# sokolov_control_board_1.net
KiCad netlist of a schematic drawn in Altium Designer
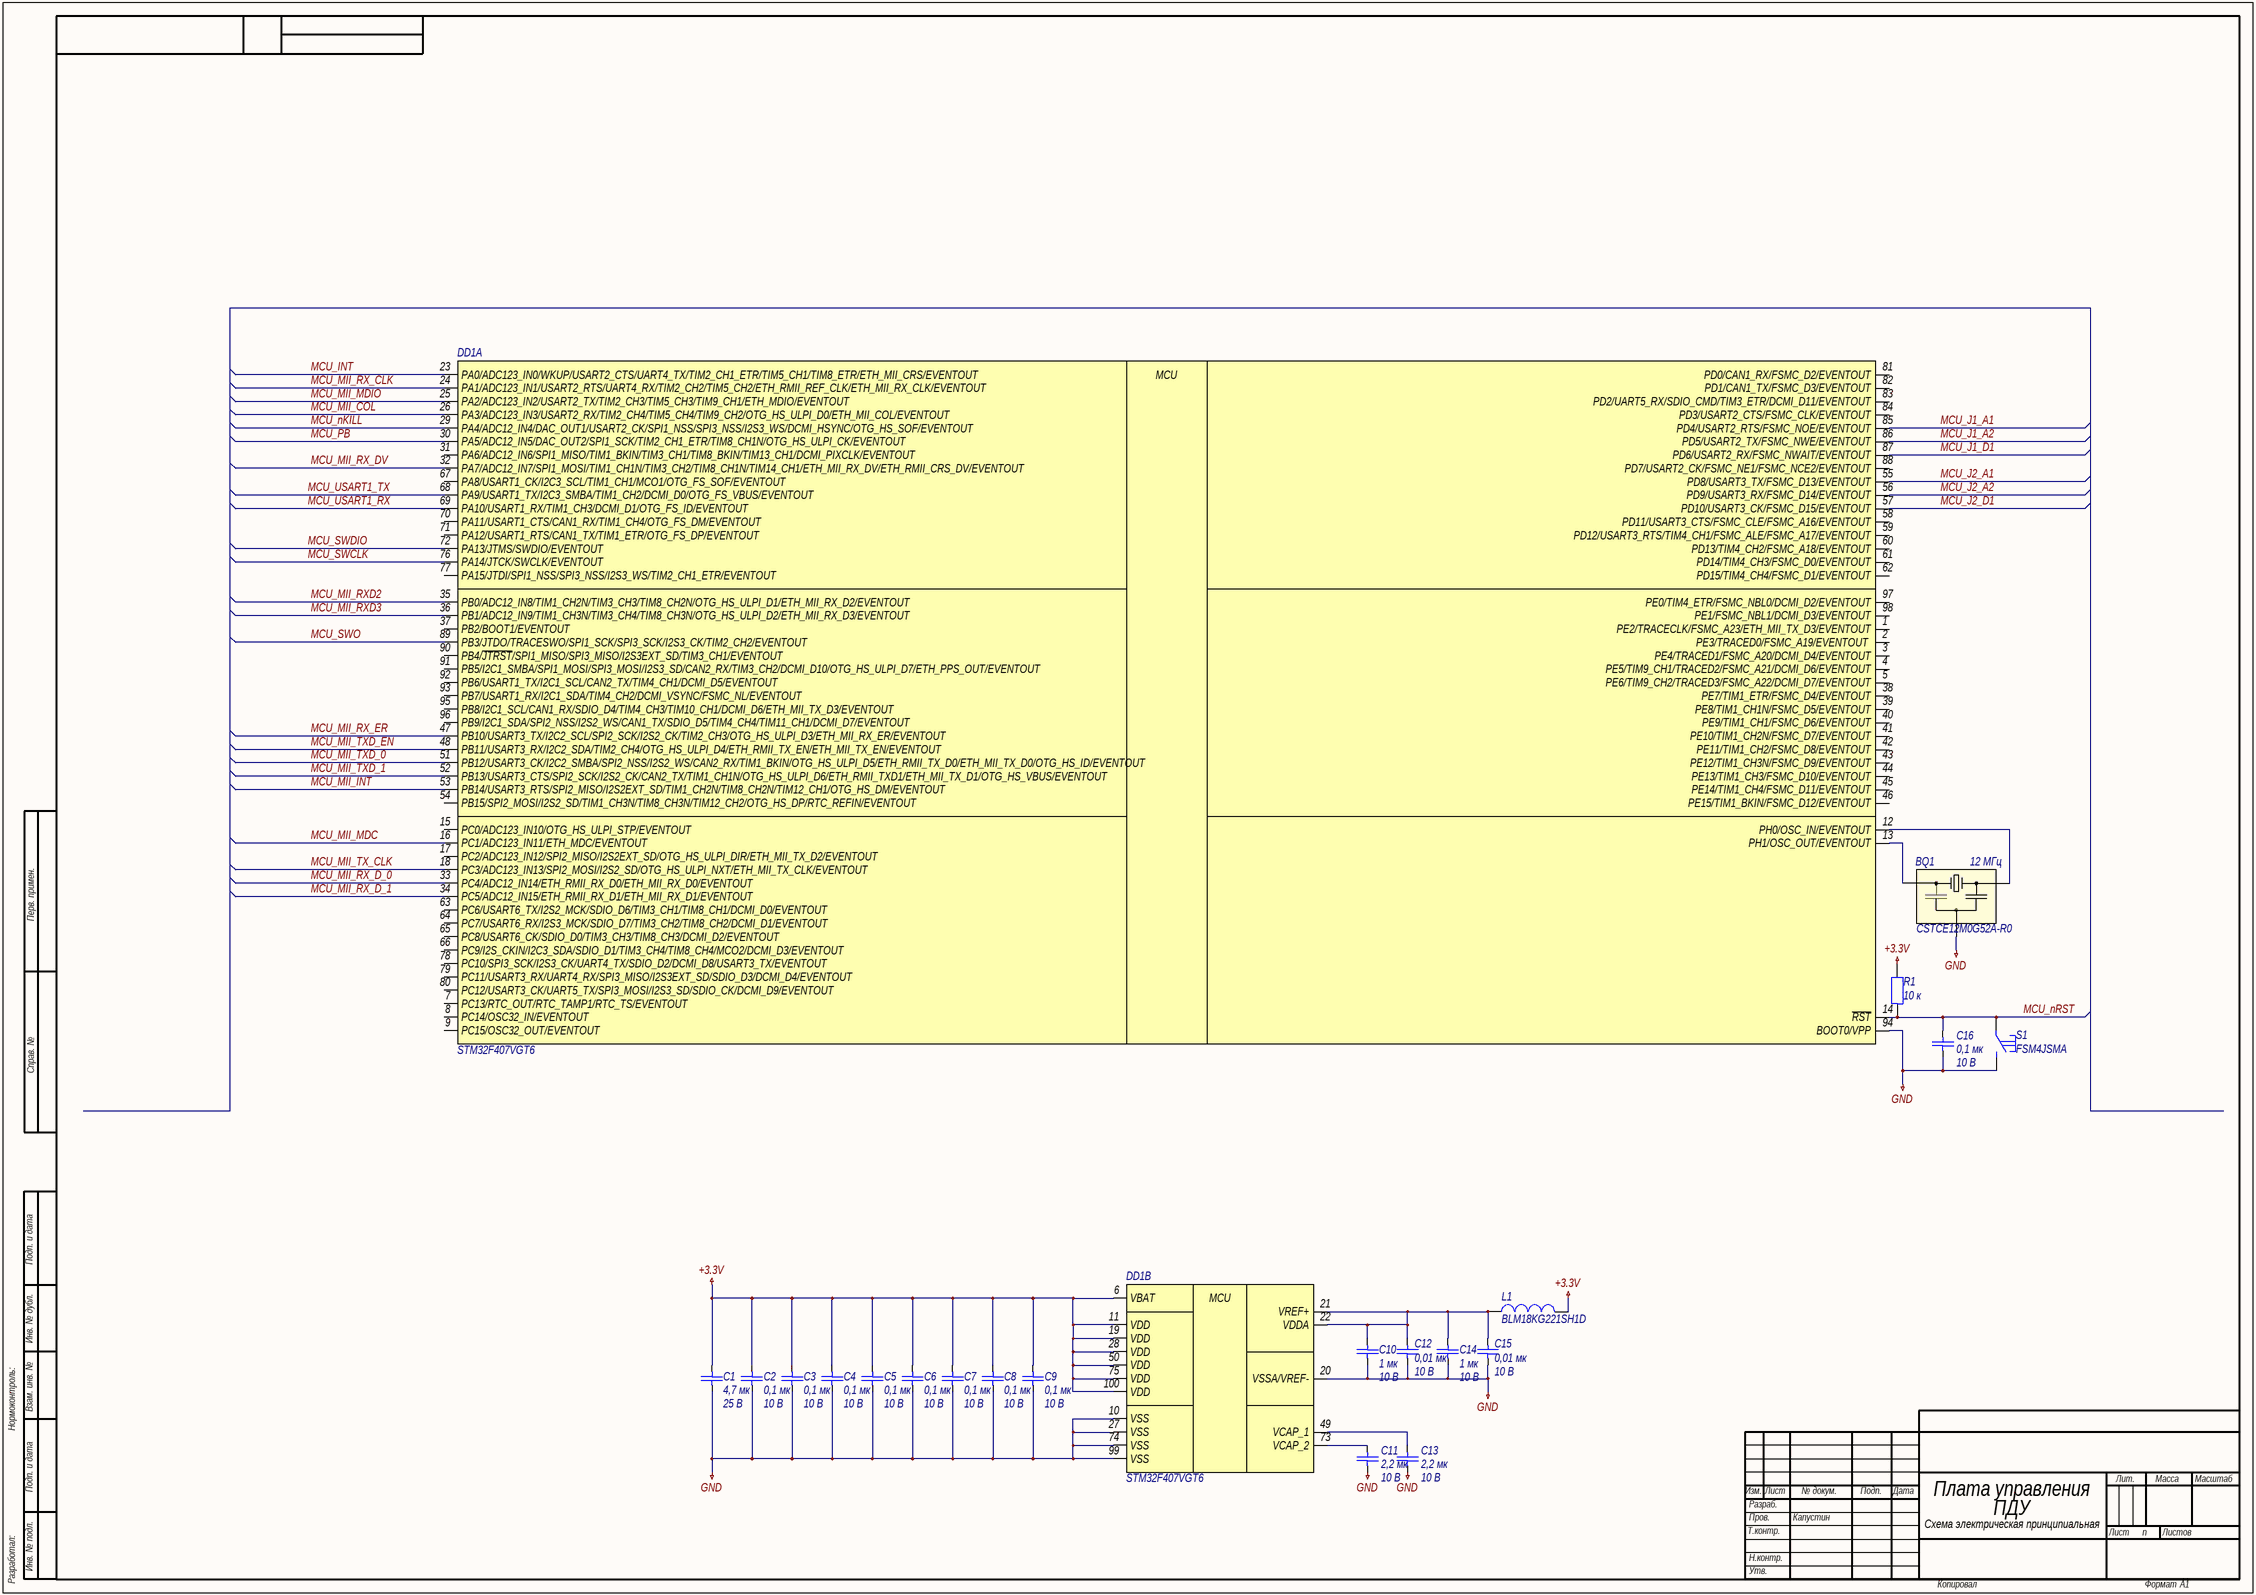
[diagram p0: sokolov_control_board_1.SchDoc]

(export (version "E")
  (design (tool "Eeschema 10.0.6"))
  (components
    (comp (ref "BQ1")
      (value "CSTCE12M0G52A-R0")
      (footprint "CSTCE-3-P120-320X130X70")
      (description "=Описание")
      (fields (field (name "ЧАСТОТA") "12 МГц"))
      (libsource (lib "Database_Students") (part "CSTCE12M0G52A-R0"))
    )
    (comp (ref "C1")
      (value "4,7 мк")
      (footprint "C0805")
      (description "=Описание")
      (fields (field (name "НАПРЯЖЕНИЕ") "25 В"))
      (libsource (lib "Database_Students") (part "CAPACITOR-NONPOLAR"))
    )
    (comp (ref "C2")
      (value "0,1 мк")
      (footprint "C0603")
      (description "=Описание")
      (fields (field (name "НАПРЯЖЕНИЕ") "10 В"))
      (libsource (lib "Database_Students") (part "CAPACITOR-NONPOLAR"))
    )
    (comp (ref "C3")
      (value "0,1 мк")
      (footprint "C0603")
      (description "=Описание")
      (fields (field (name "НАПРЯЖЕНИЕ") "10 В"))
      (libsource (lib "Database_Students") (part "CAPACITOR-NONPOLAR"))
    )
    (comp (ref "C4")
      (value "0,1 мк")
      (footprint "C0603")
      (description "=Описание")
      (fields (field (name "НАПРЯЖЕНИЕ") "10 В"))
      (libsource (lib "Database_Students") (part "CAPACITOR-NONPOLAR"))
    )
    (comp (ref "C5")
      (value "0,1 мк")
      (footprint "C0603")
      (description "=Описание")
      (fields (field (name "НАПРЯЖЕНИЕ") "10 В"))
      (libsource (lib "Database_Students") (part "CAPACITOR-NONPOLAR"))
    )
    (comp (ref "C6")
      (value "0,1 мк")
      (footprint "C0603")
      (description "=Описание")
      (fields (field (name "НАПРЯЖЕНИЕ") "10 В"))
      (libsource (lib "Database_Students") (part "CAPACITOR-NONPOLAR"))
    )
    (comp (ref "C7")
      (value "0,1 мк")
      (footprint "C0603")
      (description "=Описание")
      (fields (field (name "НАПРЯЖЕНИЕ") "10 В"))
      (libsource (lib "Database_Students") (part "CAPACITOR-NONPOLAR"))
    )
    (comp (ref "C8")
      (value "0,1 мк")
      (footprint "C0603")
      (description "=Описание")
      (fields (field (name "НАПРЯЖЕНИЕ") "10 В"))
      (libsource (lib "Database_Students") (part "CAPACITOR-NONPOLAR"))
    )
    (comp (ref "C9")
      (value "0,1 мк")
      (footprint "C0603")
      (description "=Описание")
      (fields (field (name "НАПРЯЖЕНИЕ") "10 В"))
      (libsource (lib "Database_Students") (part "CAPACITOR-NONPOLAR"))
    )
    (comp (ref "C10")
      (value "1 мк")
      (footprint "C0603")
      (description "=Описание")
      (fields (field (name "НАПРЯЖЕНИЕ") "10 В"))
      (libsource (lib "Database_Students") (part "CAPACITOR-NONPOLAR"))
    )
    (comp (ref "C11")
      (value "2,2 мк")
      (footprint "C0603")
      (description "=Описание")
      (fields (field (name "НАПРЯЖЕНИЕ") "10 В"))
      (libsource (lib "Database_Students") (part "CAPACITOR-NONPOLAR"))
    )
    (comp (ref "C12")
      (value "0,01 мк")
      (footprint "C0603")
      (description "=Описание")
      (fields (field (name "НАПРЯЖЕНИЕ") "10 В"))
      (libsource (lib "Database_Students") (part "CAPACITOR-NONPOLAR"))
    )
    (comp (ref "C13")
      (value "2,2 мк")
      (footprint "C0603")
      (description "=Описание")
      (fields (field (name "НАПРЯЖЕНИЕ") "10 В"))
      (libsource (lib "Database_Students") (part "CAPACITOR-NONPOLAR"))
    )
    (comp (ref "C14")
      (value "1 мк")
      (footprint "C0603")
      (description "=Описание")
      (fields (field (name "НАПРЯЖЕНИЕ") "10 В"))
      (libsource (lib "Database_Students") (part "CAPACITOR-NONPOLAR"))
    )
    (comp (ref "C15")
      (value "0,01 мк")
      (footprint "C0603")
      (description "=Описание")
      (fields (field (name "НАПРЯЖЕНИЕ") "10 В"))
      (libsource (lib "Database_Students") (part "CAPACITOR-NONPOLAR"))
    )
    (comp (ref "C16")
      (value "0,1 мк")
      (footprint "C0603")
      (description "=Описание")
      (fields (field (name "НАПРЯЖЕНИЕ") "10 В"))
      (libsource (lib "Database_Students") (part "CAPACITOR-NONPOLAR"))
    )
    (comp (ref "DD1")
      (value "STM32F407VGT6")
      (footprint "LQFP-100-P50-1400X1400X160-L60X22")
      (description "=Описание")
      (libsource (lib "Database_Students") (part "STM32F407VGT6"))
    )
    (comp (ref "L1")
      (value "BLM18KG221SH1D")
      (footprint "BLM-2-0603")
      (description "=Описание")
      (libsource (lib "Database_Students") (part "FERRITE-BEAD"))
    )
    (comp (ref "R1")
      (value "10 к")
      (footprint "R0603")
      (description "=Описание")
      (libsource (lib "Database_Students") (part "RESISTOR-COMMON"))
    )
    (comp (ref "S1")
      (value "FSM4JSMA")
      (footprint "FSM4JSMA")
      (description "=Описание")
      (libsource (lib "Database_Students") (part "BUTTON"))
    )
  )
  (nets
    (net (code "1") (name "+3.3V") (class "Default")
      (node (ref "C1") (pin "2") (pinfunction "2_2") (pintype "passive"))
      (node (ref "C2") (pin "2") (pinfunction "2_2") (pintype "passive"))
      (node (ref "C3") (pin "2") (pinfunction "2_2") (pintype "passive"))
      (node (ref "C4") (pin "2") (pinfunction "2_2") (pintype "passive"))
      (node (ref "C5") (pin "2") (pinfunction "2_2") (pintype "passive"))
      (node (ref "C6") (pin "2") (pinfunction "2_2") (pintype "passive"))
      (node (ref "C7") (pin "2") (pinfunction "2_2") (pintype "passive"))
      (node (ref "C8") (pin "2") (pinfunction "2_2") (pintype "passive"))
      (node (ref "C9") (pin "2") (pinfunction "2_2") (pintype "passive"))
      (node (ref "DD1") (pin "100") (pinfunction "VDD_100") (pintype "passive"))
      (node (ref "DD1") (pin "11") (pinfunction "VDD_11") (pintype "passive"))
      (node (ref "DD1") (pin "19") (pinfunction "VDD_19") (pintype "passive"))
      (node (ref "DD1") (pin "28") (pinfunction "VDD_28") (pintype "passive"))
      (node (ref "DD1") (pin "50") (pinfunction "VDD_50") (pintype "passive"))
      (node (ref "DD1") (pin "6") (pinfunction "VBAT_6") (pintype "passive"))
      (node (ref "DD1") (pin "75") (pinfunction "VDD_75") (pintype "passive"))
      (node (ref "L1") (pin "2") (pinfunction "2_2") (pintype "passive"))
      (node (ref "R1") (pin "2") (pinfunction "2_2") (pintype "passive"))
    )
    (net (code "2") (name "/MCU_INT") (class "Default")
      (node (ref "DD1") (pin "23") (pinfunction "PA0/ADC123_IN0/WKUP/USART2_CTS/UART4_TX/TIM2_CH1_ETR/TIM5_CH1/TIM8_ETR/ETH_MII_CRS/EVENTOUT_23") (pintype "passive"))
    )
    (net (code "3") (name "/MCU_J1_A1") (class "Default")
      (node (ref "DD1") (pin "85") (pinfunction "PD4/USART2_RTS/FSMC_NOE/EVENTOUT_85") (pintype "passive"))
    )
    (net (code "4") (name "/MCU_J1_A2") (class "Default")
      (node (ref "DD1") (pin "86") (pinfunction "PD5/USART2_TX/FSMC_NWE/EVENTOUT_86") (pintype "passive"))
    )
    (net (code "5") (name "/MCU_J1_D1") (class "Default")
      (node (ref "DD1") (pin "87") (pinfunction "PD6/USART2_RX/FSMC_NWAIT/EVENTOUT_87") (pintype "passive"))
    )
    (net (code "6") (name "/MCU_J2_A1") (class "Default")
      (node (ref "DD1") (pin "55") (pinfunction "PD8/USART3_TX/FSMC_D13/EVENTOUT_55") (pintype "passive"))
    )
    (net (code "7") (name "/MCU_J2_A2") (class "Default")
      (node (ref "DD1") (pin "56") (pinfunction "PD9/USART3_RX/FSMC_D14/EVENTOUT_56") (pintype "passive"))
    )
    (net (code "8") (name "/MCU_J2_D1") (class "Default")
      (node (ref "DD1") (pin "57") (pinfunction "PD10/USART3_CK/FSMC_D15/EVENTOUT_57") (pintype "passive"))
    )
    (net (code "9") (name "/MCU_MII_COL") (class "Default")
      (node (ref "DD1") (pin "26") (pinfunction "PA3/ADC123_IN3/USART2_RX/TIM2_CH4/TIM5_CH4/TIM9_CH2/OTG_HS_ULPI_D0/ETH_MII_COL/EVENTOUT_26") (pintype "passive"))
    )
    (net (code "10") (name "/MCU_MII_INT") (class "Default")
      (node (ref "DD1") (pin "53") (pinfunction "PB14/USART3_RTS/SPI2_MISO/I2S2EXT_SD/TIM1_CH2N/TIM8_CH2N/TIM12_CH1/OTG_HS_DM/EVENTOUT_53") (pintype "passive"))
    )
    (net (code "11") (name "/MCU_MII_MDC") (class "Default")
      (node (ref "DD1") (pin "16") (pinfunction "PC1/ADC123_IN11/ETH_MDC/EVENTOUT_16") (pintype "passive"))
    )
    (net (code "12") (name "/MCU_MII_MDIO") (class "Default")
      (node (ref "DD1") (pin "25") (pinfunction "PA2/ADC123_IN2/USART2_TX/TIM2_CH3/TIM5_CH3/TIM9_CH1/ETH_MDIO/EVENTOUT_25") (pintype "passive"))
    )
    (net (code "13") (name "/MCU_MII_RXD2") (class "Default")
      (node (ref "DD1") (pin "35") (pinfunction "PB0/ADC12_IN8/TIM1_CH2N/TIM3_CH3/TIM8_CH2N/OTG_HS_ULPI_D1/ETH_MII_RX_D2/EVENTOUT_35") (pintype "passive"))
    )
    (net (code "14") (name "/MCU_MII_RXD3") (class "Default")
      (node (ref "DD1") (pin "36") (pinfunction "PB1/ADC12_IN9/TIM1_CH3N/TIM3_CH4/TIM8_CH3N/OTG_HS_ULPI_D2/ETH_MII_RX_D3/EVENTOUT_36") (pintype "passive"))
    )
    (net (code "15") (name "/MCU_MII_RX_CLK") (class "Default")
      (node (ref "DD1") (pin "24") (pinfunction "PA1/ADC123_IN1/USART2_RTS/UART4_RX/TIM2_CH2/TIM5_CH2/ETH_RMII_REF_CLK/ETH_MII_RX_CLK/EVENTOUT_24") (pintype "passive"))
    )
    (net (code "16") (name "/MCU_MII_RX_DV") (class "Default")
      (node (ref "DD1") (pin "32") (pinfunction "PA7/ADC12_IN7/SPI1_MOSI/TIM1_CH1N/TIM3_CH2/TIM8_CH1N/TIM14_CH1/ETH_MII_RX_DV/ETH_RMII_CRS_DV/EVENTOUT_32") (pintype "passive"))
    )
    (net (code "17") (name "/MCU_MII_RX_D_0") (class "Default")
      (node (ref "DD1") (pin "33") (pinfunction "PC4/ADC12_IN14/ETH_RMII_RX_D0/ETH_MII_RX_D0/EVENTOUT_33") (pintype "passive"))
    )
    (net (code "18") (name "/MCU_MII_RX_D_1") (class "Default")
      (node (ref "DD1") (pin "34") (pinfunction "PC5/ADC12_IN15/ETH_RMII_RX_D1/ETH_MII_RX_D1/EVENTOUT_34") (pintype "passive"))
    )
    (net (code "19") (name "/MCU_MII_RX_ER") (class "Default")
      (node (ref "DD1") (pin "47") (pinfunction "PB10/USART3_TX/I2C2_SCL/SPI2_SCK/I2S2_CK/TIM2_CH3/OTG_HS_ULPI_D3/ETH_MII_RX_ER/EVENTOUT_47") (pintype "passive"))
    )
    (net (code "20") (name "/MCU_MII_TXD_0") (class "Default")
      (node (ref "DD1") (pin "51") (pinfunction "PB12/USART3_CK/I2C2_SMBA/SPI2_NSS/I2S2_WS/CAN2_RX/TIM1_BKIN/OTG_HS_ULPI_D5/ETH_RMII_TX_D0/ETH_MII_TX_D0/OTG_HS_ID/EVENTOUT_51") (pintype "passive"))
    )
    (net (code "21") (name "/MCU_MII_TXD_1") (class "Default")
      (node (ref "DD1") (pin "52") (pinfunction "PB13/USART3_CTS/SPI2_SCK/I2S2_CK/CAN2_TX/TIM1_CH1N/OTG_HS_ULPI_D6/ETH_RMII_TXD1/ETH_MII_TX_D1/OTG_HS_VBUS/EVENTOUT_52") (pintype "passive"))
    )
    (net (code "22") (name "/MCU_MII_TXD_EN") (class "Default")
      (node (ref "DD1") (pin "48") (pinfunction "PB11/USART3_RX/I2C2_SDA/TIM2_CH4/OTG_HS_ULPI_D4/ETH_RMII_TX_EN/ETH_MII_TX_EN/EVENTOUT_48") (pintype "passive"))
    )
    (net (code "23") (name "/MCU_MII_TX_CLK") (class "Default")
      (node (ref "DD1") (pin "18") (pinfunction "PC3/ADC123_IN13/SPI2_MOSI/I2S2_SD/OTG_HS_ULPI_NXT/ETH_MII_TX_CLK/EVENTOUT_18") (pintype "passive"))
    )
    (net (code "24") (name "/MCU_PB") (class "Default")
      (node (ref "DD1") (pin "30") (pinfunction "PA5/ADC12_IN5/DAC_OUT2/SPI1_SCK/TIM2_CH1_ETR/TIM8_CH1N/OTG_HS_ULPI_CK/EVENTOUT_30") (pintype "passive"))
    )
    (net (code "25") (name "/MCU_SWCLK") (class "Default")
      (node (ref "DD1") (pin "76") (pinfunction "PA14/JTCK/SWCLK/EVENTOUT_76") (pintype "passive"))
    )
    (net (code "26") (name "/MCU_SWDIO") (class "Default")
      (node (ref "DD1") (pin "72") (pinfunction "PA13/JTMS/SWDIO/EVENTOUT_72") (pintype "passive"))
    )
    (net (code "27") (name "/MCU_SWO") (class "Default")
      (node (ref "DD1") (pin "89") (pinfunction "PB3/JTDO/TRACESWO/SPI1_SCK/SPI3_SCK/I2S3_CK/TIM2_CH2/EVENTOUT_89") (pintype "passive"))
    )
    (net (code "28") (name "/MCU_USART1_RX") (class "Default")
      (node (ref "DD1") (pin "69") (pinfunction "PA10/USART1_RX/TIM1_CH3/DCMI_D1/OTG_FS_ID/EVENTOUT_69") (pintype "passive"))
    )
    (net (code "29") (name "/MCU_USART1_TX") (class "Default")
      (node (ref "DD1") (pin "68") (pinfunction "PA9/USART1_TX/I2C3_SMBA/TIM1_CH2/DCMI_D0/OTG_FS_VBUS/EVENTOUT_68") (pintype "passive"))
    )
    (net (code "30") (name "/MCU_nKILL") (class "Default")
      (node (ref "DD1") (pin "29") (pinfunction "PA4/ADC12_IN4/DAC_OUT1/USART2_CK/SPI1_NSS/SPI3_NSS/I2S3_WS/DCMI_HSYNC/OTG_HS_SOF/EVENTOUT_29") (pintype "passive"))
    )
    (net (code "31") (name "/MCU_nRST") (class "Default")
      (node (ref "C16") (pin "1") (pinfunction "1_1") (pintype "passive"))
      (node (ref "DD1") (pin "14") (pinfunction "~{RST}_14") (pintype "passive"))
      (node (ref "R1") (pin "1") (pinfunction "1_1") (pintype "passive"))
      (node (ref "S1") (pin "1") (pinfunction "1_1") (pintype "passive"))
    )
    (net (code "32") (name "GND") (class "Default")
      (node (ref "BQ1") (pin "2") (pinfunction "2_2") (pintype "passive"))
      (node (ref "C1") (pin "1") (pinfunction "1_1") (pintype "passive"))
      (node (ref "C10") (pin "1") (pinfunction "1_1") (pintype "passive"))
      (node (ref "C11") (pin "2") (pinfunction "2_2") (pintype "passive"))
      (node (ref "C12") (pin "2") (pinfunction "2_2") (pintype "passive"))
      (node (ref "C13") (pin "2") (pinfunction "2_2") (pintype "passive"))
      (node (ref "C14") (pin "1") (pinfunction "1_1") (pintype "passive"))
      (node (ref "C15") (pin "2") (pinfunction "2_2") (pintype "passive"))
      (node (ref "C16") (pin "2") (pinfunction "2_2") (pintype "passive"))
      (node (ref "C2") (pin "1") (pinfunction "1_1") (pintype "passive"))
      (node (ref "C3") (pin "1") (pinfunction "1_1") (pintype "passive"))
      (node (ref "C4") (pin "1") (pinfunction "1_1") (pintype "passive"))
      (node (ref "C5") (pin "1") (pinfunction "1_1") (pintype "passive"))
      (node (ref "C6") (pin "1") (pinfunction "1_1") (pintype "passive"))
      (node (ref "C7") (pin "1") (pinfunction "1_1") (pintype "passive"))
      (node (ref "C8") (pin "1") (pinfunction "1_1") (pintype "passive"))
      (node (ref "C9") (pin "1") (pinfunction "1_1") (pintype "passive"))
      (node (ref "DD1") (pin "10") (pinfunction "VSS_10") (pintype "passive"))
      (node (ref "DD1") (pin "20") (pinfunction "VSSA/VREF-_20") (pintype "passive"))
      (node (ref "DD1") (pin "27") (pinfunction "VSS_27") (pintype "passive"))
      (node (ref "DD1") (pin "74") (pinfunction "VSS_74") (pintype "passive"))
      (node (ref "DD1") (pin "94") (pinfunction "BOOT0/VPP_94") (pintype "passive"))
      (node (ref "DD1") (pin "99") (pinfunction "VSS_99") (pintype "passive"))
      (node (ref "S1") (pin "2") (pinfunction "2_2") (pintype "passive"))
    )
    (net (code "33") (name "Net-(DD1A-PH0{slash}OSC_IN{slash}EVENTOUT)") (class "Default")
      (node (ref "BQ1") (pin "1") (pinfunction "1_1") (pintype "passive"))
      (node (ref "DD1") (pin "12") (pinfunction "PH0/OSC_IN/EVENTOUT_12") (pintype "passive"))
    )
    (net (code "34") (name "Net-(DD1A-PH1{slash}OSC_OUT{slash}EVENTOUT)") (class "Default")
      (node (ref "BQ1") (pin "3") (pinfunction "3_3") (pintype "passive"))
      (node (ref "DD1") (pin "13") (pinfunction "PH1/OSC_OUT/EVENTOUT_13") (pintype "passive"))
    )
    (net (code "35") (name "Net-(DD1B-VCAP_1)") (class "Default")
      (node (ref "C13") (pin "1") (pinfunction "1_1") (pintype "passive"))
      (node (ref "DD1") (pin "49") (pinfunction "VCAP_1_49") (pintype "passive"))
    )
    (net (code "36") (name "Net-(DD1B-VCAP_2)") (class "Default")
      (node (ref "C11") (pin "1") (pinfunction "1_1") (pintype "passive"))
      (node (ref "DD1") (pin "73") (pinfunction "VCAP_2_73") (pintype "passive"))
    )
    (net (code "37") (name "Net-(DD1B-VDDA)") (class "Default")
      (node (ref "C10") (pin "2") (pinfunction "2_2") (pintype "passive"))
      (node (ref "C12") (pin "1") (pinfunction "1_1") (pintype "passive"))
      (node (ref "C14") (pin "2") (pinfunction "2_2") (pintype "passive"))
      (node (ref "C15") (pin "1") (pinfunction "1_1") (pintype "passive"))
      (node (ref "DD1") (pin "21") (pinfunction "VREF+_21") (pintype "passive"))
      (node (ref "DD1") (pin "22") (pinfunction "VDDA_22") (pintype "passive"))
      (node (ref "L1") (pin "1") (pinfunction "1_1") (pintype "passive"))
    )
    (net (code "38") (name "unconnected-(DD1A-PA6{slash}ADC12_IN6{slash}SPI1_MISO{slash}TIM1_BKIN{slash}TIM3_CH1{slash}TIM8_BKIN{slash}TIM13_CH1{slash}DCMI_PIXCLK{slash}EVENTOUT-Pad31)") (class "Default")
      (node (ref "DD1") (pin "31") (pinfunction "PA6/ADC12_IN6/SPI1_MISO/TIM1_BKIN/TIM3_CH1/TIM8_BKIN/TIM13_CH1/DCMI_PIXCLK/EVENTOUT_31") (pintype "passive"))
    )
    (net (code "39") (name "unconnected-(DD1A-PA8{slash}USART1_CK{slash}I2C3_SCL{slash}TIM1_CH1{slash}MCO1{slash}OTG_FS_SOF{slash}EVENTOUT-Pad67)") (class "Default")
      (node (ref "DD1") (pin "67") (pinfunction "PA8/USART1_CK/I2C3_SCL/TIM1_CH1/MCO1/OTG_FS_SOF/EVENTOUT_67") (pintype "passive"))
    )
    (net (code "40") (name "unconnected-(DD1A-PA11{slash}USART1_CTS{slash}CAN1_RX{slash}TIM1_CH4{slash}OTG_FS_DM{slash}EVENTOUT-Pad70)") (class "Default")
      (node (ref "DD1") (pin "70") (pinfunction "PA11/USART1_CTS/CAN1_RX/TIM1_CH4/OTG_FS_DM/EVENTOUT_70") (pintype "passive"))
    )
    (net (code "41") (name "unconnected-(DD1A-PA12{slash}USART1_RTS{slash}CAN1_TX{slash}TIM1_ETR{slash}OTG_FS_DP{slash}EVENTOUT-Pad71)") (class "Default")
      (node (ref "DD1") (pin "71") (pinfunction "PA12/USART1_RTS/CAN1_TX/TIM1_ETR/OTG_FS_DP/EVENTOUT_71") (pintype "passive"))
    )
    (net (code "42") (name "unconnected-(DD1A-PA15{slash}JTDI{slash}SPI1_NSS{slash}SPI3_NSS{slash}I2S3_WS{slash}TIM2_CH1_ETR{slash}EVENTOUT-Pad77)") (class "Default")
      (node (ref "DD1") (pin "77") (pinfunction "PA15/JTDI/SPI1_NSS/SPI3_NSS/I2S3_WS/TIM2_CH1_ETR/EVENTOUT_77") (pintype "passive"))
    )
    (net (code "43") (name "unconnected-(DD1A-PB2{slash}BOOT1{slash}EVENTOUT-Pad37)") (class "Default")
      (node (ref "DD1") (pin "37") (pinfunction "PB2/BOOT1/EVENTOUT_37") (pintype "passive"))
    )
    (net (code "44") (name "unconnected-(DD1A-PB4{slash}~{JTRST}{slash}SPI1_MISO{slash}SPI3_MISO{slash}I2S3EXT_SD{slash}TIM3_CH1{slash}EVENTOUT-Pad90)") (class "Default")
      (node (ref "DD1") (pin "90") (pinfunction "PB4/~{JTRST}/SPI1_MISO/SPI3_MISO/I2S3EXT_SD/TIM3_CH1/EVENTOUT_90") (pintype "passive"))
    )
    (net (code "45") (name "unconnected-(DD1A-PB5{slash}I2C1_SMBA{slash}SPI1_MOSI{slash}SPI3_MOSI{slash}I2S3_SD{slash}CAN2_RX{slash}TIM3_CH2{slash}DCMI_D10{slash}OTG_HS_ULPI_D7{slash}ETH_PPS_OUT{slash}EVENTOUT-Pad91)") (class "Default")
      (node (ref "DD1") (pin "91") (pinfunction "PB5/I2C1_SMBA/SPI1_MOSI/SPI3_MOSI/I2S3_SD/CAN2_RX/TIM3_CH2/DCMI_D10/OTG_HS_ULPI_D7/ETH_PPS_OUT/EVENTOUT_91") (pintype "passive"))
    )
    (net (code "46") (name "unconnected-(DD1A-PB6{slash}USART1_TX{slash}I2C1_SCL{slash}CAN2_TX{slash}TIM4_CH1{slash}DCMI_D5{slash}EVENTOUT-Pad92)") (class "Default")
      (node (ref "DD1") (pin "92") (pinfunction "PB6/USART1_TX/I2C1_SCL/CAN2_TX/TIM4_CH1/DCMI_D5/EVENTOUT_92") (pintype "passive"))
    )
    (net (code "47") (name "unconnected-(DD1A-PB7{slash}USART1_RX{slash}I2C1_SDA{slash}TIM4_CH2{slash}DCMI_VSYNC{slash}FSMC_NL{slash}EVENTOUT-Pad93)") (class "Default")
      (node (ref "DD1") (pin "93") (pinfunction "PB7/USART1_RX/I2C1_SDA/TIM4_CH2/DCMI_VSYNC/FSMC_NL/EVENTOUT_93") (pintype "passive"))
    )
    (net (code "48") (name "unconnected-(DD1A-PB8{slash}I2C1_SCL{slash}CAN1_RX{slash}SDIO_D4{slash}TIM4_CH3{slash}TIM10_CH1{slash}DCMI_D6{slash}ETH_MII_TX_D3{slash}EVENTOUT-Pad95)") (class "Default")
      (node (ref "DD1") (pin "95") (pinfunction "PB8/I2C1_SCL/CAN1_RX/SDIO_D4/TIM4_CH3/TIM10_CH1/DCMI_D6/ETH_MII_TX_D3/EVENTOUT_95") (pintype "passive"))
    )
    (net (code "49") (name "unconnected-(DD1A-PB9{slash}I2C1_SDA{slash}SPI2_NSS{slash}I2S2_WS{slash}CAN1_TX{slash}SDIO_D5{slash}TIM4_CH4{slash}TIM11_CH1{slash}DCMI_D7{slash}EVENTOUT-Pad96)") (class "Default")
      (node (ref "DD1") (pin "96") (pinfunction "PB9/I2C1_SDA/SPI2_NSS/I2S2_WS/CAN1_TX/SDIO_D5/TIM4_CH4/TIM11_CH1/DCMI_D7/EVENTOUT_96") (pintype "passive"))
    )
    (net (code "50") (name "unconnected-(DD1A-PB15{slash}SPI2_MOSI{slash}I2S2_SD{slash}TIM1_CH3N{slash}TIM8_CH3N{slash}TIM12_CH2{slash}OTG_HS_DP{slash}RTC_REFIN{slash}EVENTOUT-Pad54)") (class "Default")
      (node (ref "DD1") (pin "54") (pinfunction "PB15/SPI2_MOSI/I2S2_SD/TIM1_CH3N/TIM8_CH3N/TIM12_CH2/OTG_HS_DP/RTC_REFIN/EVENTOUT_54") (pintype "passive"))
    )
    (net (code "51") (name "unconnected-(DD1A-PC0{slash}ADC123_IN10{slash}OTG_HS_ULPI_STP{slash}EVENTOUT-Pad15)") (class "Default")
      (node (ref "DD1") (pin "15") (pinfunction "PC0/ADC123_IN10/OTG_HS_ULPI_STP/EVENTOUT_15") (pintype "passive"))
    )
    (net (code "52") (name "unconnected-(DD1A-PC2{slash}ADC123_IN12{slash}SPI2_MISO{slash}I2S2EXT_SD{slash}OTG_HS_ULPI_DIR{slash}ETH_MII_TX_D2{slash}EVENTOUT-Pad17)") (class "Default")
      (node (ref "DD1") (pin "17") (pinfunction "PC2/ADC123_IN12/SPI2_MISO/I2S2EXT_SD/OTG_HS_ULPI_DIR/ETH_MII_TX_D2/EVENTOUT_17") (pintype "passive"))
    )
    (net (code "53") (name "unconnected-(DD1A-PC6{slash}USART6_TX{slash}I2S2_MCK{slash}SDIO_D6{slash}TIM3_CH1{slash}TIM8_CH1{slash}DCMI_D0{slash}EVENTOUT-Pad63)") (class "Default")
      (node (ref "DD1") (pin "63") (pinfunction "PC6/USART6_TX/I2S2_MCK/SDIO_D6/TIM3_CH1/TIM8_CH1/DCMI_D0/EVENTOUT_63") (pintype "passive"))
    )
    (net (code "54") (name "unconnected-(DD1A-PC7{slash}USART6_RX{slash}I2S3_MCK{slash}SDIO_D7{slash}TIM3_CH2{slash}TIM8_CH2{slash}DCMI_D1{slash}EVENTOUT-Pad64)") (class "Default")
      (node (ref "DD1") (pin "64") (pinfunction "PC7/USART6_RX/I2S3_MCK/SDIO_D7/TIM3_CH2/TIM8_CH2/DCMI_D1/EVENTOUT_64") (pintype "passive"))
    )
    (net (code "55") (name "unconnected-(DD1A-PC8{slash}USART6_CK{slash}SDIO_D0{slash}TIM3_CH3{slash}TIM8_CH3{slash}DCMI_D2{slash}EVENTOUT-Pad65)") (class "Default")
      (node (ref "DD1") (pin "65") (pinfunction "PC8/USART6_CK/SDIO_D0/TIM3_CH3/TIM8_CH3/DCMI_D2/EVENTOUT_65") (pintype "passive"))
    )
    (net (code "56") (name "unconnected-(DD1A-PC9{slash}I2S_CKIN{slash}I2C3_SDA{slash}SDIO_D1{slash}TIM3_CH4{slash}TIM8_CH4{slash}MCO2{slash}DCMI_D3{slash}EVENTOUT-Pad66)") (class "Default")
      (node (ref "DD1") (pin "66") (pinfunction "PC9/I2S_CKIN/I2C3_SDA/SDIO_D1/TIM3_CH4/TIM8_CH4/MCO2/DCMI_D3/EVENTOUT_66") (pintype "passive"))
    )
    (net (code "57") (name "unconnected-(DD1A-PC10{slash}SPI3_SCK{slash}I2S3_CK{slash}UART4_TX{slash}SDIO_D2{slash}DCMI_D8{slash}USART3_TX{slash}EVENTOUT-Pad78)") (class "Default")
      (node (ref "DD1") (pin "78") (pinfunction "PC10/SPI3_SCK/I2S3_CK/UART4_TX/SDIO_D2/DCMI_D8/USART3_TX/EVENTOUT_78") (pintype "passive"))
    )
    (net (code "58") (name "unconnected-(DD1A-PC11{slash}USART3_RX{slash}UART4_RX{slash}SPI3_MISO{slash}I2S3EXT_SD{slash}SDIO_D3{slash}DCMI_D4{slash}EVENTOUT-Pad79)") (class "Default")
      (node (ref "DD1") (pin "79") (pinfunction "PC11/USART3_RX/UART4_RX/SPI3_MISO/I2S3EXT_SD/SDIO_D3/DCMI_D4/EVENTOUT_79") (pintype "passive"))
    )
    (net (code "59") (name "unconnected-(DD1A-PC12{slash}USART3_CK{slash}UART5_TX{slash}SPI3_MOSI{slash}I2S3_SD{slash}SDIO_CK{slash}DCMI_D9{slash}EVENTOUT-Pad80)") (class "Default")
      (node (ref "DD1") (pin "80") (pinfunction "PC12/USART3_CK/UART5_TX/SPI3_MOSI/I2S3_SD/SDIO_CK/DCMI_D9/EVENTOUT_80") (pintype "passive"))
    )
    (net (code "60") (name "unconnected-(DD1A-PC13{slash}RTC_OUT{slash}RTC_TAMP1{slash}RTC_TS{slash}EVENTOUT-Pad7)") (class "Default")
      (node (ref "DD1") (pin "7") (pinfunction "PC13/RTC_OUT/RTC_TAMP1/RTC_TS/EVENTOUT_7") (pintype "passive"))
    )
    (net (code "61") (name "unconnected-(DD1A-PC14{slash}OSC32_IN{slash}EVENTOUT-Pad8)") (class "Default")
      (node (ref "DD1") (pin "8") (pinfunction "PC14/OSC32_IN/EVENTOUT_8") (pintype "passive"))
    )
    (net (code "62") (name "unconnected-(DD1A-PC15{slash}OSC32_OUT{slash}EVENTOUT-Pad9)") (class "Default")
      (node (ref "DD1") (pin "9") (pinfunction "PC15/OSC32_OUT/EVENTOUT_9") (pintype "passive"))
    )
    (net (code "63") (name "unconnected-(DD1A-PD0{slash}CAN1_RX{slash}FSMC_D2{slash}EVENTOUT-Pad81)") (class "Default")
      (node (ref "DD1") (pin "81") (pinfunction "PD0/CAN1_RX/FSMC_D2/EVENTOUT_81") (pintype "passive"))
    )
    (net (code "64") (name "unconnected-(DD1A-PD1{slash}CAN1_TX{slash}FSMC_D3{slash}EVENTOUT-Pad82)") (class "Default")
      (node (ref "DD1") (pin "82") (pinfunction "PD1/CAN1_TX/FSMC_D3/EVENTOUT_82") (pintype "passive"))
    )
    (net (code "65") (name "unconnected-(DD1A-PD2{slash}UART5_RX{slash}SDIO_CMD{slash}TIM3_ETR{slash}DCMI_D11{slash}EVENTOUT-Pad83)") (class "Default")
      (node (ref "DD1") (pin "83") (pinfunction "PD2/UART5_RX/SDIO_CMD/TIM3_ETR/DCMI_D11/EVENTOUT_83") (pintype "passive"))
    )
    (net (code "66") (name "unconnected-(DD1A-PD3{slash}USART2_CTS{slash}FSMC_CLK{slash}EVENTOUT-Pad84)") (class "Default")
      (node (ref "DD1") (pin "84") (pinfunction "PD3/USART2_CTS/FSMC_CLK/EVENTOUT_84") (pintype "passive"))
    )
    (net (code "67") (name "unconnected-(DD1A-PD7{slash}USART2_CK{slash}FSMC_NE1{slash}FSMC_NCE2{slash}EVENTOUT-Pad88)") (class "Default")
      (node (ref "DD1") (pin "88") (pinfunction "PD7/USART2_CK/FSMC_NE1/FSMC_NCE2/EVENTOUT_88") (pintype "passive"))
    )
    (net (code "68") (name "unconnected-(DD1A-PD11{slash}USART3_CTS{slash}FSMC_CLE{slash}FSMC_A16{slash}EVENTOUT-Pad58)") (class "Default")
      (node (ref "DD1") (pin "58") (pinfunction "PD11/USART3_CTS/FSMC_CLE/FSMC_A16/EVENTOUT_58") (pintype "passive"))
    )
    (net (code "69") (name "unconnected-(DD1A-PD12{slash}USART3_RTS{slash}TIM4_CH1{slash}FSMC_ALE{slash}FSMC_A17{slash}EVENTOUT-Pad59)") (class "Default")
      (node (ref "DD1") (pin "59") (pinfunction "PD12/USART3_RTS/TIM4_CH1/FSMC_ALE/FSMC_A17/EVENTOUT_59") (pintype "passive"))
    )
    (net (code "70") (name "unconnected-(DD1A-PD13{slash}TIM4_CH2{slash}FSMC_A18{slash}EVENTOUT-Pad60)") (class "Default")
      (node (ref "DD1") (pin "60") (pinfunction "PD13/TIM4_CH2/FSMC_A18/EVENTOUT_60") (pintype "passive"))
    )
    (net (code "71") (name "unconnected-(DD1A-PD14{slash}TIM4_CH3{slash}FSMC_D0{slash}EVENTOUT-Pad61)") (class "Default")
      (node (ref "DD1") (pin "61") (pinfunction "PD14/TIM4_CH3/FSMC_D0/EVENTOUT_61") (pintype "passive"))
    )
    (net (code "72") (name "unconnected-(DD1A-PD15{slash}TIM4_CH4{slash}FSMC_D1{slash}EVENTOUT-Pad62)") (class "Default")
      (node (ref "DD1") (pin "62") (pinfunction "PD15/TIM4_CH4/FSMC_D1/EVENTOUT_62") (pintype "passive"))
    )
    (net (code "73") (name "unconnected-(DD1A-PE0{slash}TIM4_ETR{slash}FSMC_NBL0{slash}DCMI_D2{slash}EVENTOUT-Pad97)") (class "Default")
      (node (ref "DD1") (pin "97") (pinfunction "PE0/TIM4_ETR/FSMC_NBL0/DCMI_D2/EVENTOUT_97") (pintype "passive"))
    )
    (net (code "74") (name "unconnected-(DD1A-PE1{slash}FSMC_NBL1{slash}DCMI_D3{slash}EVENTOUT-Pad98)") (class "Default")
      (node (ref "DD1") (pin "98") (pinfunction "PE1/FSMC_NBL1/DCMI_D3/EVENTOUT_98") (pintype "passive"))
    )
    (net (code "75") (name "unconnected-(DD1A-PE2{slash}TRACECLK{slash}FSMC_A23{slash}ETH_MII_TX_D3{slash}EVENTOUT-Pad1)") (class "Default")
      (node (ref "DD1") (pin "1") (pinfunction "PE2/TRACECLK/FSMC_A23/ETH_MII_TX_D3/EVENTOUT_1") (pintype "passive"))
    )
    (net (code "76") (name "unconnected-(DD1A-PE3{slash}TRACED0{slash}FSMC_A19{slash}EVENTOUT-Pad2)") (class "Default")
      (node (ref "DD1") (pin "2") (pinfunction "PE3/TRACED0/FSMC_A19/EVENTOUT_2") (pintype "passive"))
    )
    (net (code "77") (name "unconnected-(DD1A-PE4{slash}TRACED1{slash}FSMC_A20{slash}DCMI_D4{slash}EVENTOUT-Pad3)") (class "Default")
      (node (ref "DD1") (pin "3") (pinfunction "PE4/TRACED1/FSMC_A20/DCMI_D4/EVENTOUT_3") (pintype "passive"))
    )
    (net (code "78") (name "unconnected-(DD1A-PE5{slash}TIM9_CH1{slash}TRACED2{slash}FSMC_A21{slash}DCMI_D6{slash}EVENTOUT-Pad4)") (class "Default")
      (node (ref "DD1") (pin "4") (pinfunction "PE5/TIM9_CH1/TRACED2/FSMC_A21/DCMI_D6/EVENTOUT_4") (pintype "passive"))
    )
    (net (code "79") (name "unconnected-(DD1A-PE6{slash}TIM9_CH2{slash}TRACED3{slash}FSMC_A22{slash}DCMI_D7{slash}EVENTOUT-Pad5)") (class "Default")
      (node (ref "DD1") (pin "5") (pinfunction "PE6/TIM9_CH2/TRACED3/FSMC_A22/DCMI_D7/EVENTOUT_5") (pintype "passive"))
    )
    (net (code "80") (name "unconnected-(DD1A-PE7{slash}TIM1_ETR{slash}FSMC_D4{slash}EVENTOUT-Pad38)") (class "Default")
      (node (ref "DD1") (pin "38") (pinfunction "PE7/TIM1_ETR/FSMC_D4/EVENTOUT_38") (pintype "passive"))
    )
    (net (code "81") (name "unconnected-(DD1A-PE8{slash}TIM1_CH1N{slash}FSMC_D5{slash}EVENTOUT-Pad39)") (class "Default")
      (node (ref "DD1") (pin "39") (pinfunction "PE8/TIM1_CH1N/FSMC_D5/EVENTOUT_39") (pintype "passive"))
    )
    (net (code "82") (name "unconnected-(DD1A-PE9{slash}TIM1_CH1{slash}FSMC_D6{slash}EVENTOUT-Pad40)") (class "Default")
      (node (ref "DD1") (pin "40") (pinfunction "PE9/TIM1_CH1/FSMC_D6/EVENTOUT_40") (pintype "passive"))
    )
    (net (code "83") (name "unconnected-(DD1A-PE10{slash}TIM1_CH2N{slash}FSMC_D7{slash}EVENTOUT-Pad41)") (class "Default")
      (node (ref "DD1") (pin "41") (pinfunction "PE10/TIM1_CH2N/FSMC_D7/EVENTOUT_41") (pintype "passive"))
    )
    (net (code "84") (name "unconnected-(DD1A-PE11{slash}TIM1_CH2{slash}FSMC_D8{slash}EVENTOUT-Pad42)") (class "Default")
      (node (ref "DD1") (pin "42") (pinfunction "PE11/TIM1_CH2/FSMC_D8/EVENTOUT_42") (pintype "passive"))
    )
    (net (code "85") (name "unconnected-(DD1A-PE12{slash}TIM1_CH3N{slash}FSMC_D9{slash}EVENTOUT-Pad43)") (class "Default")
      (node (ref "DD1") (pin "43") (pinfunction "PE12/TIM1_CH3N/FSMC_D9/EVENTOUT_43") (pintype "passive"))
    )
    (net (code "86") (name "unconnected-(DD1A-PE13{slash}TIM1_CH3{slash}FSMC_D10{slash}EVENTOUT-Pad44)") (class "Default")
      (node (ref "DD1") (pin "44") (pinfunction "PE13/TIM1_CH3/FSMC_D10/EVENTOUT_44") (pintype "passive"))
    )
    (net (code "87") (name "unconnected-(DD1A-PE14{slash}TIM1_CH4{slash}FSMC_D11{slash}EVENTOUT-Pad45)") (class "Default")
      (node (ref "DD1") (pin "45") (pinfunction "PE14/TIM1_CH4/FSMC_D11/EVENTOUT_45") (pintype "passive"))
    )
    (net (code "88") (name "unconnected-(DD1A-PE15{slash}TIM1_BKIN{slash}FSMC_D12{slash}EVENTOUT-Pad46)") (class "Default")
      (node (ref "DD1") (pin "46") (pinfunction "PE15/TIM1_BKIN/FSMC_D12/EVENTOUT_46") (pintype "passive"))
    )
  )
)
